# Vref.net
KiCad netlist of a schematic drawn in Altium Designer
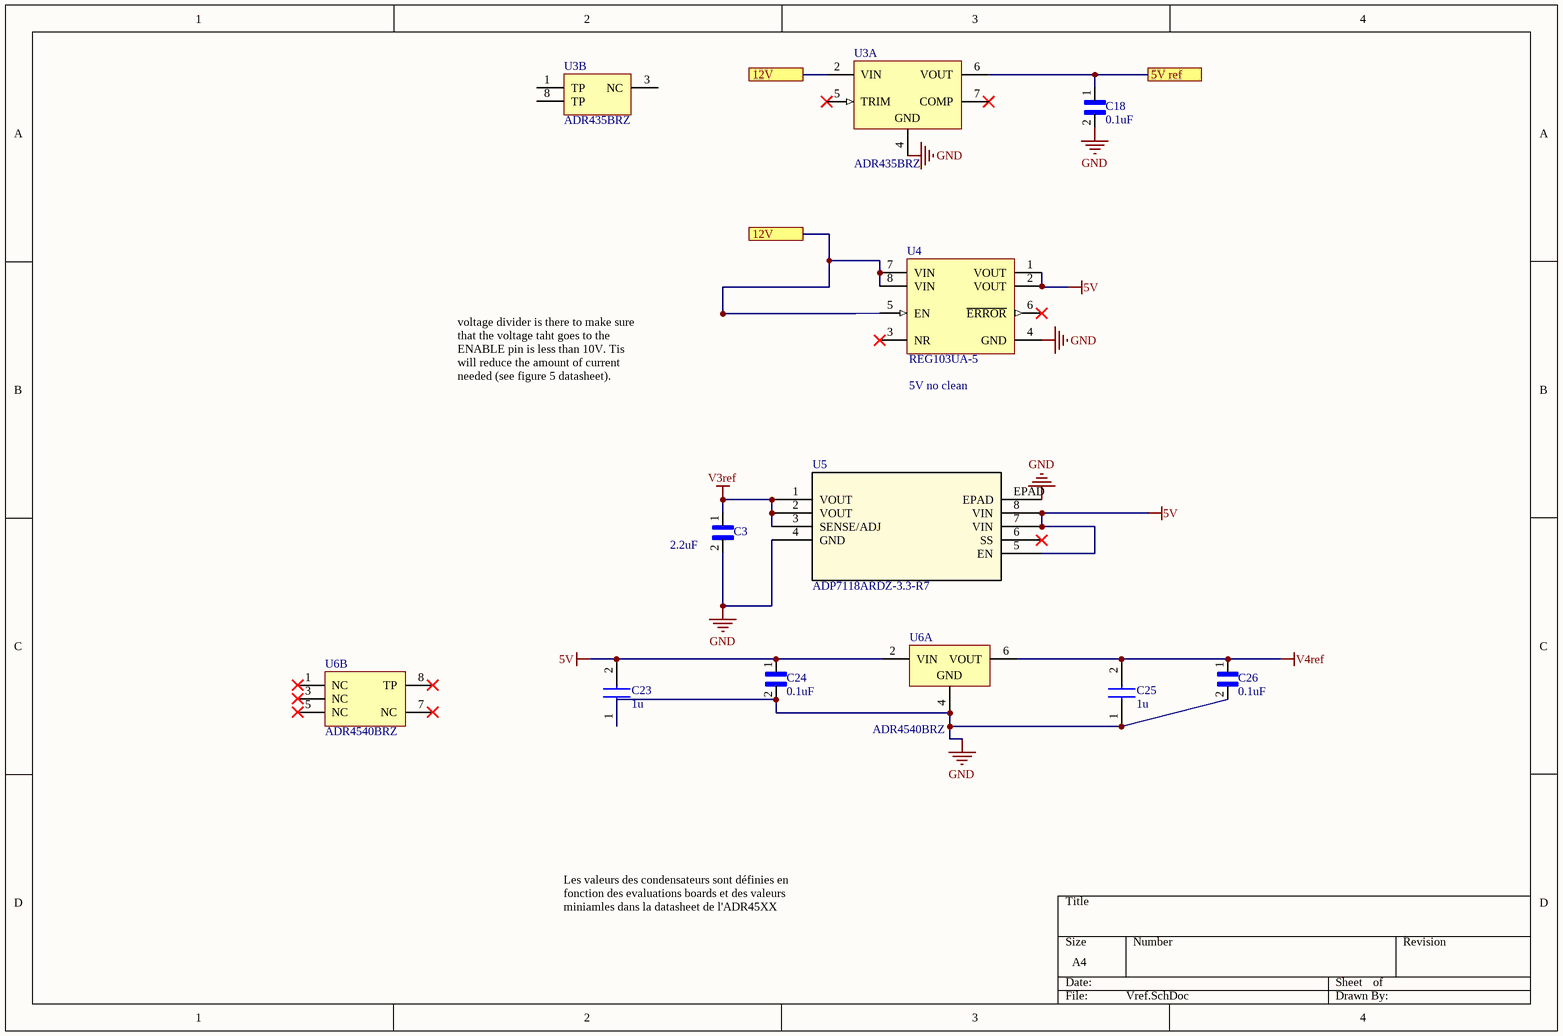
[diagram p0: Vref.SchDoc]

(export (version "E")
  (design (tool "Eeschema 10.0.6"))
  (components
    (comp (ref "C3")
      (value "2.2uF")
      (footprint "CAPC1608X90")
      (description "2.2UF 16V 20%")
      (fields (field (name "MP") "F981C225MMA") (field (name "MF") "{'manufacturer': u'AVX'}"))
      (libsource (lib "GIGUL") (part "Symbol"))
    )
    (comp (ref "C18")
      (value "0.1uF")
      (footprint "CAPC1608X90N")
      (description "Cap Ceramic 0.1uF 25V X5R 10% SMD 0603 85ÂÂŽ T/R")
      (fields (field (name "MP") "06033D104KAT2A") (field (name "MF") "{'manufacturer': u'AVX'}"))
      (libsource (lib "GIGUL") (part "06033D104KAT2A"))
    )
    (comp (ref "C23")
      (value "1u")
      (footprint "CAPC1608X90N")
      (description "Capacitor")
      (fields (field (name "MANUFACTURER_PART_NUMBER") "0603YC105MAT4A"))
      (libsource (lib "GIGUL") (part "0603YC105MAT4A"))
    )
    (comp (ref "C24")
      (value "0.1uF")
      (footprint "CAPC1608X90N")
      (description "Cap Ceramic 0.1uF 25V X5R 10% SMD 0603 85ÂÂŽ T/R")
      (fields (field (name "MP") "06033D104KAT2A") (field (name "MF") "{'manufacturer': u'AVX'}"))
      (libsource (lib "GIGUL") (part "06033D104KAT2A"))
    )
    (comp (ref "C25")
      (value "1u")
      (footprint "CAPC1608X90N")
      (description "Capacitor")
      (fields (field (name "MANUFACTURER_PART_NUMBER") "0603YC105MAT4A"))
      (libsource (lib "GIGUL") (part "0603YC105MAT4A"))
    )
    (comp (ref "C26")
      (value "0.1uF")
      (footprint "CAPC1608X90N")
      (description "Cap Ceramic 0.1uF 25V X5R 10% SMD 0603 85ÂÂŽ T/R")
      (fields (field (name "MP") "06033D104KAT2A") (field (name "MF") "{'manufacturer': u'AVX'}"))
      (libsource (lib "GIGUL") (part "06033D104KAT2A"))
    )
    (comp (ref "U3")
      (value "ADR435BRZ")
      (footprint "ADI-R-8_M")
      (fields (field (name "MANUFACTURER") "Analog Devices"))
      (libsource (lib "GIGUL") (part "CMP-0784-00226-1"))
    )
    (comp (ref "U4")
      (value "REG103UA-5")
      (footprint "D0008A_M")
      (fields (field (name "MANUFACTURER") "Texas Instruments"))
      (libsource (lib "GIGUL") (part "CMP-0395-00135-2"))
    )
    (comp (ref "U5")
      (value "ADP7118ARDZ-3.3-R7")
      (footprint "SOIC_08_EP_3P9X4P9_ADI")
      (description "No Description Available")
      (fields (field (name "COPYRIGHT") "Copyright (C) 2021 Ultra Librarian. All rights reserved."))
      (libsource (lib "GIGUL") (part "ADP7118ARDZ-3.3-R7"))
    )
    (comp (ref "U6")
      (value "ADR4540BRZ")
      (footprint "ADI-R-8_M")
      (fields (field (name "MANUFACTURER") "Analog Devices"))
      (libsource (lib "GIGUL") (part "CMP-0784-00192-1"))
    )
  )
  (nets
    (net (code "1") (name "/5V ref") (class "Default")
      (node (ref "C18") (pin "1") (pinfunction "1_1") (pintype "passive"))
      (node (ref "U3") (pin "6") (pinfunction "VOUT_6") (pintype "power_in"))
    )
    (net (code "2") (name "/12V") (class "Default")
      (node (ref "U3") (pin "2") (pinfunction "VIN_2") (pintype "power_in"))
      (node (ref "U4") (pin "5") (pinfunction "EN_5") (pintype "input"))
      (node (ref "U4") (pin "7") (pinfunction "VIN_7") (pintype "power_in"))
      (node (ref "U4") (pin "8") (pinfunction "VIN_8") (pintype "power_in"))
    )
    (net (code "3") (name "5V") (class "Default")
      (node (ref "C23") (pin "2") (pinfunction "2_2") (pintype "passive"))
      (node (ref "C24") (pin "1") (pinfunction "1_1") (pintype "passive"))
      (node (ref "U4") (pin "1") (pinfunction "VOUT_1") (pintype "power_in"))
      (node (ref "U4") (pin "2") (pinfunction "VOUT_2") (pintype "power_in"))
      (node (ref "U5") (pin "5") (pinfunction "EN_5") (pintype "passive"))
      (node (ref "U5") (pin "7") (pinfunction "VIN_7") (pintype "passive"))
      (node (ref "U5") (pin "8") (pinfunction "VIN_8") (pintype "passive"))
      (node (ref "U6") (pin "2") (pinfunction "VIN_2") (pintype "power_in"))
    )
    (net (code "4") (name "GND") (class "Default")
      (node (ref "C18") (pin "2") (pinfunction "2_2") (pintype "passive"))
      (node (ref "C23") (pin "1") (pinfunction "1_1") (pintype "passive"))
      (node (ref "C24") (pin "2") (pinfunction "2_2") (pintype "passive"))
      (node (ref "C25") (pin "1") (pinfunction "1_1") (pintype "passive"))
      (node (ref "C26") (pin "2") (pinfunction "2_2") (pintype "passive"))
      (node (ref "C3") (pin "2") (pinfunction "2_2") (pintype "passive"))
      (node (ref "U3") (pin "4") (pinfunction "GND_4") (pintype "power_in"))
      (node (ref "U4") (pin "4") (pinfunction "GND_4") (pintype "power_in"))
      (node (ref "U5") (pin "4") (pinfunction "GND_4") (pintype "passive"))
      (node (ref "U5") (pin "EPAD") (pinfunction "EPAD_EPAD") (pintype "passive"))
      (node (ref "U6") (pin "4") (pinfunction "GND_4") (pintype "power_in"))
    )
    (net (code "5") (name "V3ref") (class "Default")
      (node (ref "C3") (pin "1") (pinfunction "1_1") (pintype "passive"))
      (node (ref "U5") (pin "1") (pinfunction "VOUT_1") (pintype "power_in"))
      (node (ref "U5") (pin "2") (pinfunction "VOUT_2") (pintype "power_in"))
      (node (ref "U5") (pin "3") (pinfunction "SENSE/ADJ_3") (pintype "passive"))
    )
    (net (code "6") (name "V4ref") (class "Default")
      (node (ref "C25") (pin "2") (pinfunction "2_2") (pintype "passive"))
      (node (ref "C26") (pin "1") (pinfunction "1_1") (pintype "passive"))
      (node (ref "U6") (pin "6") (pinfunction "VOUT_6") (pintype "power_in"))
    )
    (net (code "7") (name "unconnected-(U3A-COMP-Pad7)") (class "Default")
      (node (ref "U3") (pin "7") (pinfunction "COMP_7") (pintype "passive+no_connect"))
    )
    (net (code "8") (name "unconnected-(U3A-TRIM-Pad5)") (class "Default")
      (node (ref "U3") (pin "5") (pinfunction "TRIM_5") (pintype "input+no_connect"))
    )
    (net (code "9") (name "unconnected-(U3B-NC-Pad3)") (class "Default")
      (node (ref "U3") (pin "3") (pinfunction "NC_3") (pintype "passive"))
    )
    (net (code "10") (name "unconnected-(U3B-TP-Pad1)") (class "Default")
      (node (ref "U3") (pin "1") (pinfunction "TP_1") (pintype "passive"))
    )
    (net (code "11") (name "unconnected-(U3B-TP-Pad8)") (class "Default")
      (node (ref "U3") (pin "8") (pinfunction "TP_8") (pintype "passive"))
    )
    (net (code "12") (name "unconnected-(U4-NR-Pad3)") (class "Default")
      (node (ref "U4") (pin "3") (pinfunction "NR_3") (pintype "passive+no_connect"))
    )
    (net (code "13") (name "unconnected-(U4-~{ERROR}-Pad6)") (class "Default")
      (node (ref "U4") (pin "6") (pinfunction "~{ERROR}_6") (pintype "output+no_connect"))
    )
    (net (code "14") (name "unconnected-(U5-SS-Pad6)") (class "Default")
      (node (ref "U5") (pin "6") (pinfunction "SS_6") (pintype "passive+no_connect"))
    )
    (net (code "15") (name "unconnected-(U6B-NC-Pad1)") (class "Default")
      (node (ref "U6") (pin "1") (pinfunction "NC_1") (pintype "passive+no_connect"))
    )
    (net (code "16") (name "unconnected-(U6B-NC-Pad3)") (class "Default")
      (node (ref "U6") (pin "3") (pinfunction "NC_3") (pintype "passive+no_connect"))
    )
    (net (code "17") (name "unconnected-(U6B-NC-Pad5)") (class "Default")
      (node (ref "U6") (pin "5") (pinfunction "NC_5") (pintype "passive+no_connect"))
    )
    (net (code "18") (name "unconnected-(U6B-NC-Pad7)") (class "Default")
      (node (ref "U6") (pin "7") (pinfunction "NC_7") (pintype "passive+no_connect"))
    )
    (net (code "19") (name "unconnected-(U6B-TP-Pad8)") (class "Default")
      (node (ref "U6") (pin "8") (pinfunction "TP_8") (pintype "passive+no_connect"))
    )
  )
)
